# ProPrj_ESP32___2025-01-06.net
KiCad netlist of a schematic drawn in EasyEDA Pro
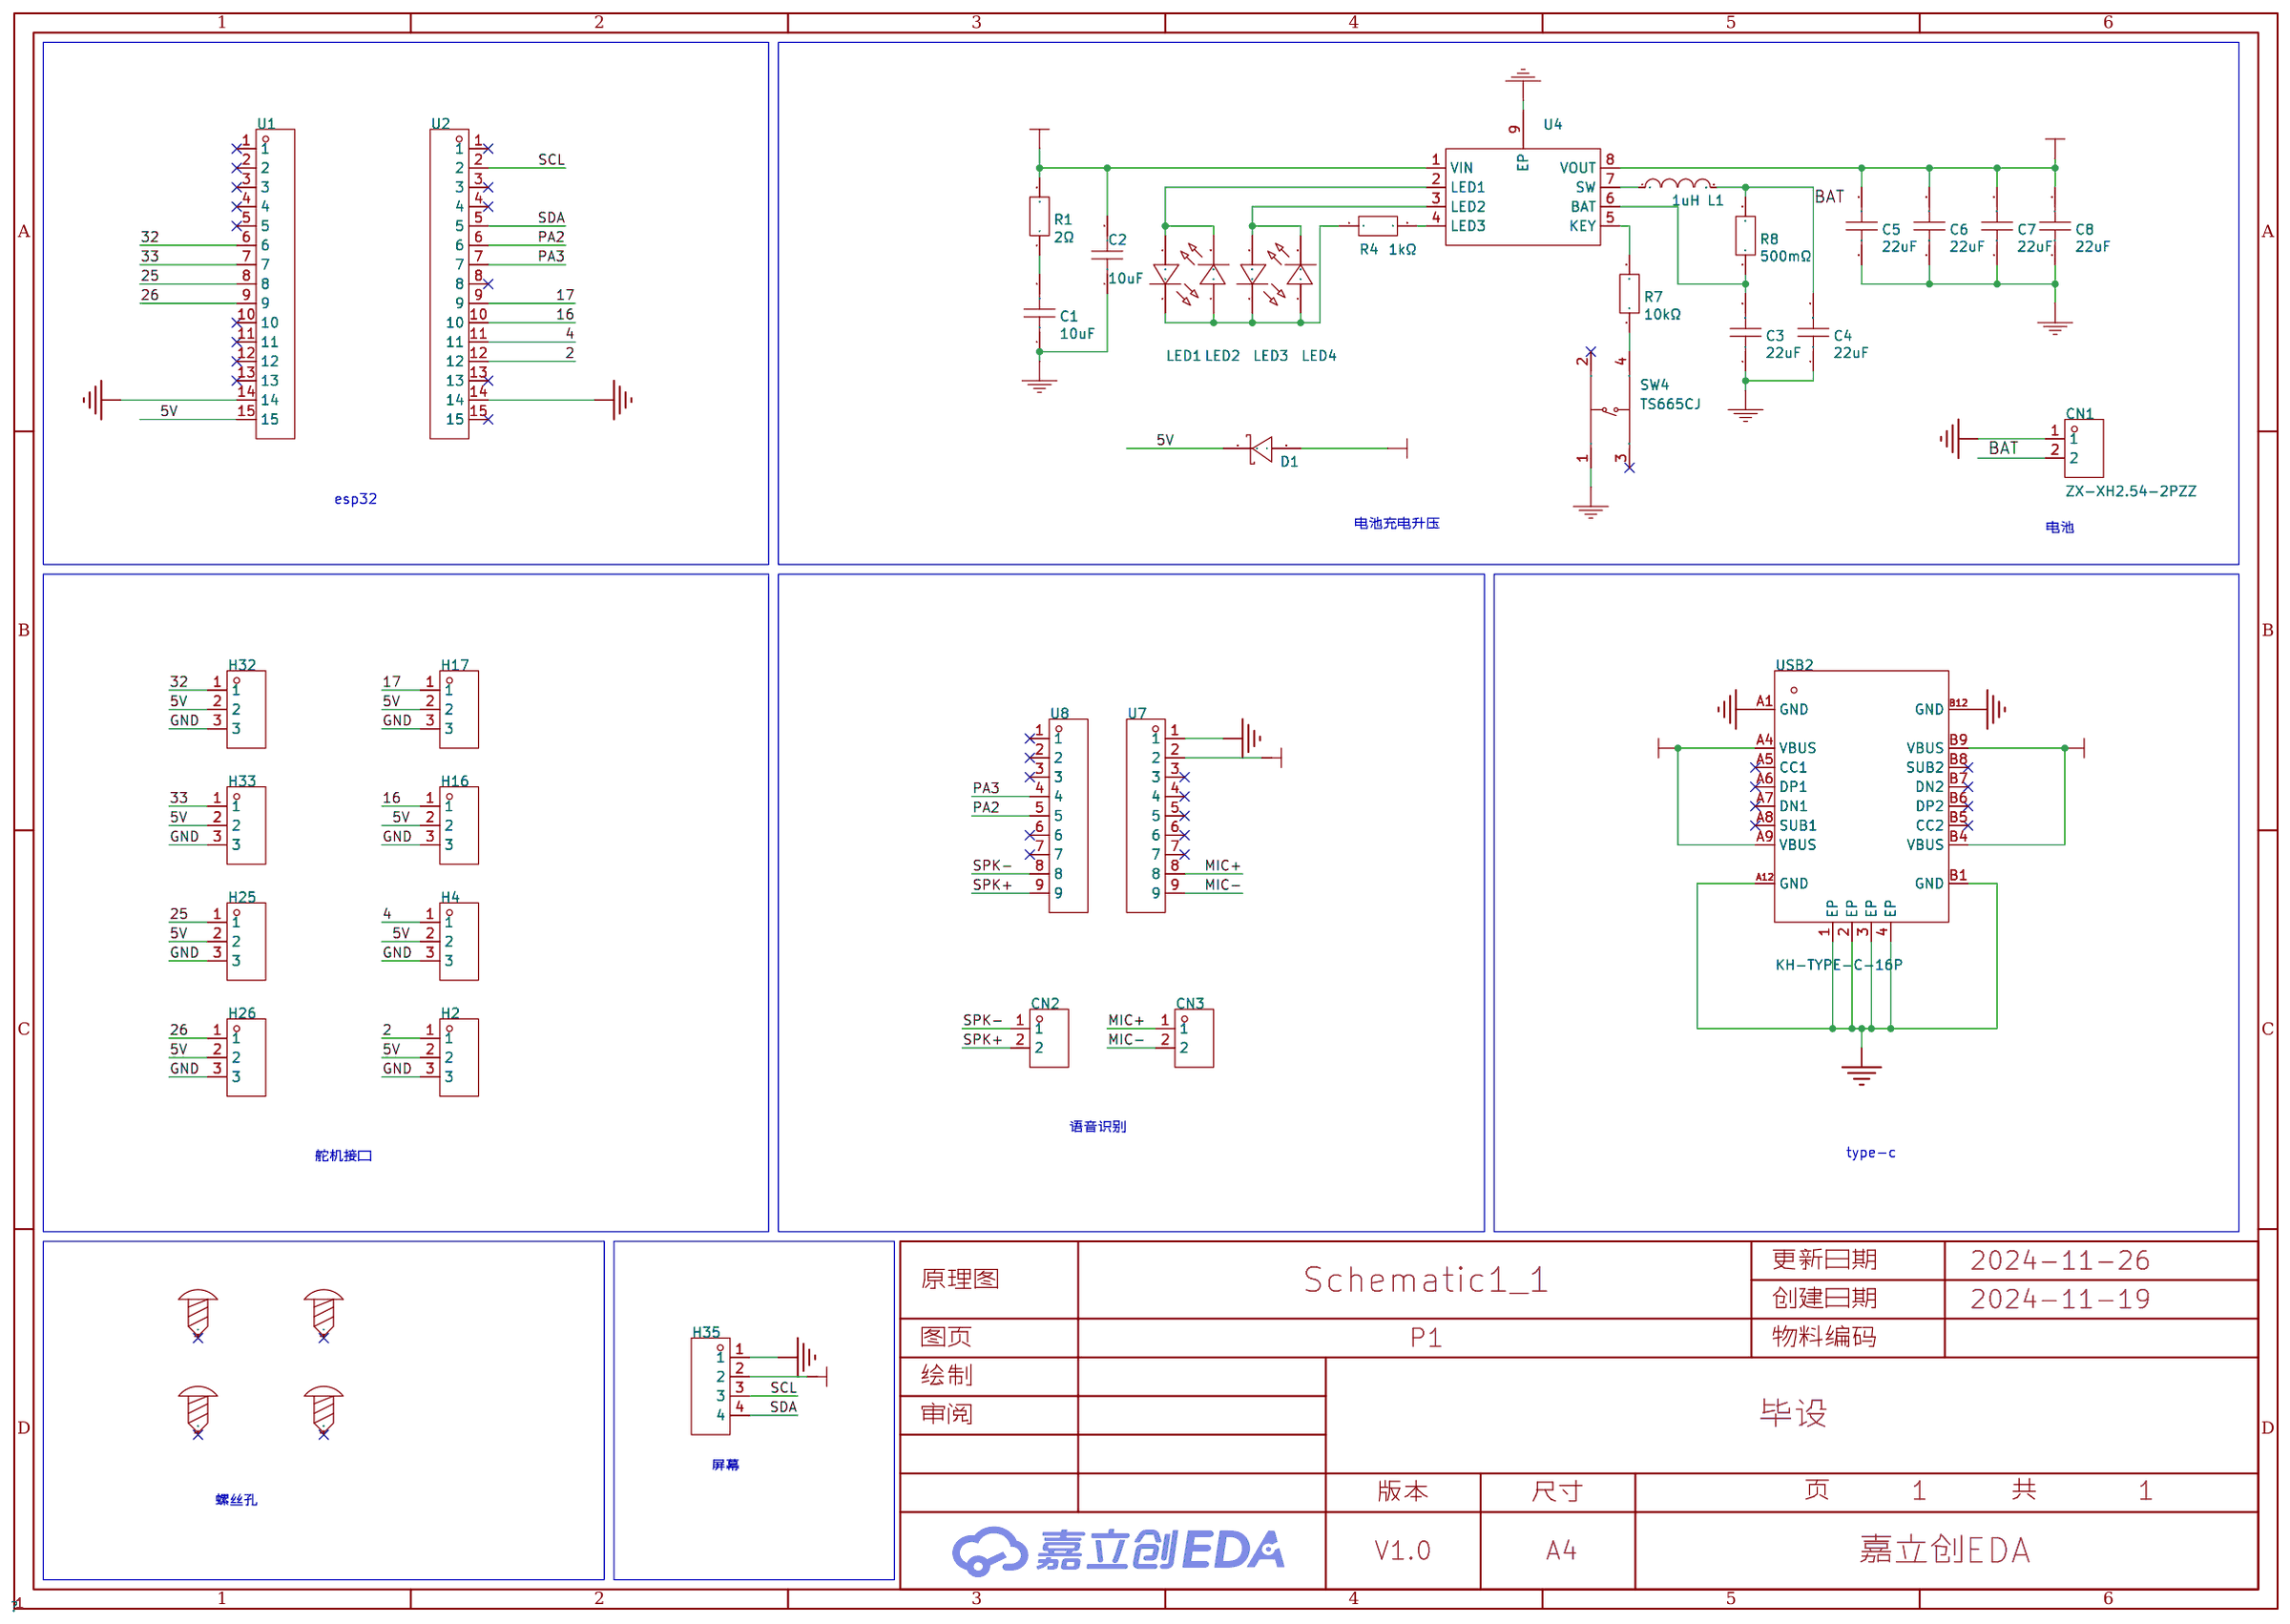
[diagram p0: schematic sheet]

(export (version "E")
  (design (tool "Eeschema 10.0.6"))
  (components
    (comp (ref "C1")
      (value "10uF")
      (fields (field (name "Manufacturer") "SAMSUNG(三星)"))
      (libsource (lib "easyedapro") (part "10u"))
    )
    (comp (ref "C2")
      (value "10uF")
      (fields (field (name "Manufacturer") "SAMSUNG(三星)"))
      (libsource (lib "easyedapro") (part "10u"))
    )
    (comp (ref "C3")
      (value "22uF")
      (fields (field (name "Manufacturer") "SAMSUNG(三星)"))
      (libsource (lib "easyedapro") (part "22u"))
    )
    (comp (ref "C4")
      (value "22uF")
      (fields (field (name "Manufacturer") "SAMSUNG(三星)"))
      (libsource (lib "easyedapro") (part "22u"))
    )
    (comp (ref "C5")
      (value "22uF")
      (fields (field (name "Manufacturer") "SAMSUNG(三星)"))
      (libsource (lib "easyedapro") (part "22u"))
    )
    (comp (ref "C6")
      (value "22uF")
      (fields (field (name "Manufacturer") "SAMSUNG(三星)"))
      (libsource (lib "easyedapro") (part "22u"))
    )
    (comp (ref "C7")
      (value "22uF")
      (fields (field (name "Manufacturer") "SAMSUNG(三星)"))
      (libsource (lib "easyedapro") (part "22u"))
    )
    (comp (ref "C8")
      (value "22uF")
      (fields (field (name "Manufacturer") "SAMSUNG(三星)"))
      (libsource (lib "easyedapro") (part "22u"))
    )
    (comp (ref "CN1")
      (value "ZX-XH2.54-2PZZ")
      (footprint "easyedapro:CONN-TH_2P-P2.50_HX25003-2A")
      (fields (field (name "Manufacturer") "Megastar(兆星)"))
      (libsource (lib "easyedapro") (part "ZX-XH2.54-2PZZ"))
    )
    (comp (ref "CN2")
      (value "ZX-XH2.54-2PZZ")
      (footprint "easyedapro:CONN-TH_2P-P2.50_HX25003-2A")
      (fields (field (name "Manufacturer") "Megastar(兆星)"))
      (libsource (lib "easyedapro") (part "ZX-XH2.54-2PZZ"))
    )
    (comp (ref "CN3")
      (value "ZX-XH2.54-2PZZ")
      (footprint "easyedapro:CONN-TH_2P-P2.50_HX25003-2A")
      (fields (field (name "Manufacturer") "Megastar(兆星)"))
      (libsource (lib "easyedapro") (part "ZX-XH2.54-2PZZ"))
    )
    (comp (ref "D1")
      (value "SS32")
      (fields (field (name "Manufacturer") "Jingdao"))
      (libsource (lib "easyedapro") (part "SS32"))
    )
    (comp (ref "H2")
      (value "PZ254V-11-03P")
      (footprint "easyedapro:HDR-TH_3P-P2.54-V-M")
      (fields (field (name "Manufacturer") "XFCN(兴飞)"))
      (libsource (lib "easyedapro") (part "PZ254V-11-03P_C2937625"))
    )
    (comp (ref "H4")
      (value "PZ254V-11-03P")
      (footprint "easyedapro:HDR-TH_3P-P2.54-V-M")
      (fields (field (name "Manufacturer") "XFCN(兴飞)"))
      (libsource (lib "easyedapro") (part "PZ254V-11-03P_C2937625"))
    )
    (comp (ref "H16")
      (value "PZ254V-11-03P")
      (footprint "easyedapro:HDR-TH_3P-P2.54-V-M")
      (fields (field (name "Manufacturer") "XFCN(兴飞)"))
      (libsource (lib "easyedapro") (part "PZ254V-11-03P_C2937625"))
    )
    (comp (ref "H17")
      (value "PZ254V-11-03P")
      (footprint "easyedapro:HDR-TH_3P-P2.54-V-M")
      (fields (field (name "Manufacturer") "XFCN(兴飞)"))
      (libsource (lib "easyedapro") (part "PZ254V-11-03P_C2937625"))
    )
    (comp (ref "H25")
      (value "PZ254V-11-03P")
      (footprint "easyedapro:HDR-TH_3P-P2.54-V-M")
      (fields (field (name "Manufacturer") "XFCN(兴飞)"))
      (libsource (lib "easyedapro") (part "PZ254V-11-03P_C2937625"))
    )
    (comp (ref "H26")
      (value "PZ254V-11-03P")
      (footprint "easyedapro:HDR-TH_3P-P2.54-V-M")
      (fields (field (name "Manufacturer") "XFCN(兴飞)"))
      (libsource (lib "easyedapro") (part "PZ254V-11-03P_C2937625"))
    )
    (comp (ref "H32")
      (value "PZ254V-11-03P")
      (footprint "easyedapro:HDR-TH_3P-P2.54-V-M")
      (fields (field (name "Manufacturer") "XFCN(兴飞)"))
      (libsource (lib "easyedapro") (part "PZ254V-11-03P_C2937625"))
    )
    (comp (ref "H33")
      (value "PZ254V-11-03P")
      (footprint "easyedapro:HDR-TH_3P-P2.54-V-M")
      (fields (field (name "Manufacturer") "XFCN(兴飞)"))
      (libsource (lib "easyedapro") (part "PZ254V-11-03P_C2937625"))
    )
    (comp (ref "H35")
      (value "2.54-1*4P母")
      (footprint "easyedapro:HDR-TH_4P-P2.54-V-F")
      (fields (field (name "Manufacturer") "BOOMELE(博穆精密)"))
      (libsource (lib "easyedapro") (part "2.54-1*4P母"))
    )
    (comp (ref "L1")
      (value "1uH")
      (fields (field (name "Manufacturer Part") "SPM6530T-1R0M120") (field (name "Manufacturer") "TDK"))
      (libsource (lib "easyedapro") (part "1uH"))
    )
    (comp (ref "LED1")
      (value "NCD0805G1")
      (fields (field (name "Manufacturer") "国星光电"))
      (libsource (lib "easyedapro") (part "0805_G"))
    )
    (comp (ref "LED2")
      (value "NCD0805G1")
      (fields (field (name "Manufacturer") "国星光电"))
      (libsource (lib "easyedapro") (part "0805_G"))
    )
    (comp (ref "LED3")
      (value "NCD0805G1")
      (fields (field (name "Manufacturer") "国星光电"))
      (libsource (lib "easyedapro") (part "0805_G"))
    )
    (comp (ref "LED4")
      (value "NCD0805G1")
      (fields (field (name "Manufacturer") "国星光电"))
      (libsource (lib "easyedapro") (part "0805_G"))
    )
    (comp (ref "R1")
      (value "2Ω")
      (fields (field (name "Manufacturer") "FOJAN(富捷)"))
      (libsource (lib "easyedapro") (part "2R"))
    )
    (comp (ref "R4")
      (value "1kΩ")
      (fields (field (name "Manufacturer") "UNI-ROYAL(厚声)"))
      (libsource (lib "easyedapro") (part "1K"))
    )
    (comp (ref "R7")
      (value "10kΩ")
      (fields (field (name "Manufacturer") "UNI-ROYAL(厚声)"))
      (libsource (lib "easyedapro") (part "10k"))
    )
    (comp (ref "R8")
      (value "500mΩ")
      (fields (field (name "Manufacturer") "FOJAN(富捷)"))
      (libsource (lib "easyedapro") (part "0.5R"))
    )
    (comp (ref "SCREW1")
      (value "~")
      (footprint "easyedapro:M4螺丝")
      (libsource (lib "easyedapro") (part "螺丝孔"))
    )
    (comp (ref "SCREW2")
      (value "~")
      (footprint "easyedapro:M4螺丝")
      (libsource (lib "easyedapro") (part "螺丝孔"))
    )
    (comp (ref "SCREW3")
      (value "~")
      (footprint "easyedapro:M4螺丝")
      (libsource (lib "easyedapro") (part "螺丝孔"))
    )
    (comp (ref "SCREW4")
      (value "~")
      (footprint "easyedapro:M4螺丝")
      (libsource (lib "easyedapro") (part "螺丝孔"))
    )
    (comp (ref "SW4")
      (value "TS665CJ")
      (footprint "easyedapro:SW-TH_4P-L6.0-W6.0-P4.50-LS6.5")
      (description "电路结构:单刀单掷;按钮形状:圆形按钮;安装方式:直插;开关长度:6mm;开关宽度:6mm;开关高度:5mm;触点电流:50mA;额定电压(DC):12V;带灯:-;机械寿命:-;")
      (fields (field (name "Manufacturer") "SHOU HAN(首韩)"))
      (libsource (lib "easyedapro") (part "TS665CJ"))
    )
    (comp (ref "U1")
      (value "KH-2.54FH-1X15P-H8.5")
      (footprint "easyedapro:HDR-TH_15P-P2.54-V-F")
      (fields (field (name "Manufacturer") "kinghelm(金航标)"))
      (libsource (lib "easyedapro") (part "KH-2.54FH-1X15P-H8.5"))
    )
    (comp (ref "U2")
      (value "KH-2.54FH-1X15P-H8.5")
      (footprint "easyedapro:HDR-TH_15P-P2.54-V-F")
      (fields (field (name "Manufacturer") "kinghelm(金航标)"))
      (libsource (lib "easyedapro") (part "KH-2.54FH-1X15P-H8.5"))
    )
    (comp (ref "U4")
      (value "IP5306")
      (fields (field (name "Manufacturer") "INJOINIC"))
      (libsource (lib "easyedapro") (part "IP5306"))
    )
    (comp (ref "U7")
      (value "PM254-1-09-Z-8.5")
      (footprint "easyedapro:HDR-TH_9P-P2.54-V-F")
      (fields (field (name "Manufacturer") "HCTL(华灿天禄)"))
      (libsource (lib "easyedapro") (part "PM254-1-09-Z-8.5"))
    )
    (comp (ref "U8")
      (value "PM254-1-09-Z-8.5")
      (footprint "easyedapro:HDR-TH_9P-P2.54-V-F")
      (fields (field (name "Manufacturer") "HCTL(华灿天禄)"))
      (libsource (lib "easyedapro") (part "PM254-1-09-Z-8.5"))
    )
    (comp (ref "USB2")
      (value "KH-TYPE-C-16P")
      (footprint "easyedapro:usb-c-smd_kh-type-c-16p")
      (description "连接器类型:Type-C;标准:-;公母:母;端口数量:1;触点数量:16P;安装方式:卧贴;额定电流 - 电源:3A;工作温度范围:-40°C~+85°C;")
      (fields (field (name "Manufacturer") "kinghelm(金航标)"))
      (libsource (lib "easyedapro") (part "KH-TYPE-C-16P"))
    )
  )
  (nets
    (net (code "1") (name "/2") (class "Default")
      (node (ref "H2") (pin "1") (pinfunction "1_1") (pintype "unspecified"))
      (node (ref "U2") (pin "12") (pinfunction "12_12") (pintype "unspecified"))
    )
    (net (code "2") (name "/4") (class "Default")
      (node (ref "H4") (pin "1") (pinfunction "1_1") (pintype "unspecified"))
      (node (ref "U2") (pin "11") (pinfunction "11_11") (pintype "unspecified"))
    )
    (net (code "3") (name "/16") (class "Default")
      (node (ref "H16") (pin "1") (pinfunction "1_1") (pintype "unspecified"))
      (node (ref "U2") (pin "10") (pinfunction "10_10") (pintype "unspecified"))
    )
    (net (code "4") (name "/17") (class "Default")
      (node (ref "H17") (pin "1") (pinfunction "1_1") (pintype "unspecified"))
      (node (ref "U2") (pin "9") (pinfunction "9_9") (pintype "unspecified"))
    )
    (net (code "5") (name "/25") (class "Default")
      (node (ref "H25") (pin "1") (pinfunction "1_1") (pintype "unspecified"))
      (node (ref "U1") (pin "8") (pinfunction "8_8") (pintype "unspecified"))
    )
    (net (code "6") (name "/26") (class "Default")
      (node (ref "H26") (pin "1") (pinfunction "1_1") (pintype "unspecified"))
      (node (ref "U1") (pin "9") (pinfunction "9_9") (pintype "unspecified"))
    )
    (net (code "7") (name "/32") (class "Default")
      (node (ref "H32") (pin "1") (pinfunction "1_1") (pintype "unspecified"))
      (node (ref "U1") (pin "6") (pinfunction "6_6") (pintype "unspecified"))
    )
    (net (code "8") (name "/33") (class "Default")
      (node (ref "H33") (pin "1") (pinfunction "1_1") (pintype "unspecified"))
      (node (ref "U1") (pin "7") (pinfunction "7_7") (pintype "unspecified"))
    )
    (net (code "9") (name "/BAT") (class "Default")
      (node (ref "C4") (pin "2") (pinfunction "2_2") (pintype "unspecified"))
      (node (ref "CN1") (pin "2") (pinfunction "2_2") (pintype "unspecified"))
      (node (ref "L1") (pin "2") (pinfunction "2_2") (pintype "unspecified"))
      (node (ref "R8") (pin "2") (pinfunction "2_2") (pintype "unspecified"))
    )
    (net (code "10") (name "/MIC+") (class "Default")
      (node (ref "CN3") (pin "1") (pinfunction "1_1") (pintype "unspecified"))
      (node (ref "U7") (pin "8") (pinfunction "8_8") (pintype "unspecified"))
    )
    (net (code "11") (name "/MIC-") (class "Default")
      (node (ref "CN3") (pin "2") (pinfunction "2_2") (pintype "unspecified"))
      (node (ref "U7") (pin "9") (pinfunction "9_9") (pintype "unspecified"))
    )
    (net (code "12") (name "/PA2") (class "Default")
      (node (ref "U2") (pin "6") (pinfunction "6_6") (pintype "unspecified"))
      (node (ref "U8") (pin "5") (pinfunction "5_5") (pintype "unspecified"))
    )
    (net (code "13") (name "/PA3") (class "Default")
      (node (ref "U2") (pin "7") (pinfunction "7_7") (pintype "unspecified"))
      (node (ref "U8") (pin "4") (pinfunction "4_4") (pintype "unspecified"))
    )
    (net (code "14") (name "/SCL") (class "Default")
      (node (ref "H35") (pin "3") (pinfunction "3_3") (pintype "unspecified"))
      (node (ref "U2") (pin "2") (pinfunction "2_2") (pintype "unspecified"))
    )
    (net (code "15") (name "/SDA") (class "Default")
      (node (ref "H35") (pin "4") (pinfunction "4_4") (pintype "unspecified"))
      (node (ref "U2") (pin "5") (pinfunction "5_5") (pintype "unspecified"))
    )
    (net (code "16") (name "/SPK+") (class "Default")
      (node (ref "CN2") (pin "2") (pinfunction "2_2") (pintype "unspecified"))
      (node (ref "U8") (pin "9") (pinfunction "9_9") (pintype "unspecified"))
    )
    (net (code "17") (name "/SPK-") (class "Default")
      (node (ref "CN2") (pin "1") (pinfunction "1_1") (pintype "unspecified"))
      (node (ref "U8") (pin "8") (pinfunction "8_8") (pintype "unspecified"))
    )
    (net (code "18") (name "5V") (class "Default")
      (node (ref "D1") (pin "1") (pinfunction "K_1") (pintype "unspecified"))
      (node (ref "H16") (pin "2") (pinfunction "2_2") (pintype "unspecified"))
      (node (ref "H17") (pin "2") (pinfunction "2_2") (pintype "unspecified"))
      (node (ref "H2") (pin "2") (pinfunction "2_2") (pintype "unspecified"))
      (node (ref "H25") (pin "2") (pinfunction "2_2") (pintype "unspecified"))
      (node (ref "H26") (pin "2") (pinfunction "2_2") (pintype "unspecified"))
      (node (ref "H32") (pin "2") (pinfunction "2_2") (pintype "unspecified"))
      (node (ref "H33") (pin "2") (pinfunction "2_2") (pintype "unspecified"))
      (node (ref "H35") (pin "2") (pinfunction "2_2") (pintype "unspecified"))
      (node (ref "H4") (pin "2") (pinfunction "2_2") (pintype "unspecified"))
      (node (ref "U1") (pin "15") (pinfunction "15_15") (pintype "unspecified"))
      (node (ref "U7") (pin "2") (pinfunction "2_2") (pintype "unspecified"))
    )
    (net (code "19") (name "5VOUT") (class "Default")
      (node (ref "C5") (pin "2") (pinfunction "2_2") (pintype "unspecified"))
      (node (ref "C6") (pin "2") (pinfunction "2_2") (pintype "unspecified"))
      (node (ref "C7") (pin "2") (pinfunction "2_2") (pintype "unspecified"))
      (node (ref "C8") (pin "2") (pinfunction "2_2") (pintype "unspecified"))
      (node (ref "D1") (pin "2") (pinfunction "A_2") (pintype "unspecified"))
      (node (ref "U4") (pin "8") (pinfunction "VOUT_8") (pintype "unspecified"))
    )
    (net (code "20") (name "GND") (class "Default")
      (node (ref "C1") (pin "1") (pinfunction "1_1") (pintype "unspecified"))
      (node (ref "C2") (pin "1") (pinfunction "1_1") (pintype "unspecified"))
      (node (ref "C3") (pin "1") (pinfunction "1_1") (pintype "unspecified"))
      (node (ref "C4") (pin "1") (pinfunction "1_1") (pintype "unspecified"))
      (node (ref "C5") (pin "1") (pinfunction "1_1") (pintype "unspecified"))
      (node (ref "C6") (pin "1") (pinfunction "1_1") (pintype "unspecified"))
      (node (ref "C7") (pin "1") (pinfunction "1_1") (pintype "unspecified"))
      (node (ref "C8") (pin "1") (pinfunction "1_1") (pintype "unspecified"))
      (node (ref "CN1") (pin "1") (pinfunction "1_1") (pintype "unspecified"))
      (node (ref "H16") (pin "3") (pinfunction "3_3") (pintype "unspecified"))
      (node (ref "H17") (pin "3") (pinfunction "3_3") (pintype "unspecified"))
      (node (ref "H2") (pin "3") (pinfunction "3_3") (pintype "unspecified"))
      (node (ref "H25") (pin "3") (pinfunction "3_3") (pintype "unspecified"))
      (node (ref "H26") (pin "3") (pinfunction "3_3") (pintype "unspecified"))
      (node (ref "H32") (pin "3") (pinfunction "3_3") (pintype "unspecified"))
      (node (ref "H33") (pin "3") (pinfunction "3_3") (pintype "unspecified"))
      (node (ref "H35") (pin "1") (pinfunction "1_1") (pintype "unspecified"))
      (node (ref "H4") (pin "3") (pinfunction "3_3") (pintype "unspecified"))
      (node (ref "SW4") (pin "1") (pinfunction "A_1") (pintype "unspecified"))
      (node (ref "U1") (pin "14") (pinfunction "14_14") (pintype "unspecified"))
      (node (ref "U2") (pin "14") (pinfunction "14_14") (pintype "unspecified"))
      (node (ref "U4") (pin "9") (pinfunction "EP_9") (pintype "unspecified"))
      (node (ref "U7") (pin "1") (pinfunction "1_1") (pintype "unspecified"))
      (node (ref "USB2") (pin "1") (pinfunction "EP_1") (pintype "unspecified"))
      (node (ref "USB2") (pin "2") (pinfunction "EP_2") (pintype "unspecified"))
      (node (ref "USB2") (pin "3") (pinfunction "EP_3") (pintype "unspecified"))
      (node (ref "USB2") (pin "4") (pinfunction "EP_4") (pintype "unspecified"))
      (node (ref "USB2") (pin "A1") (pinfunction "GND_A1") (pintype "unspecified"))
      (node (ref "USB2") (pin "A12") (pinfunction "GND_A12") (pintype "unspecified"))
      (node (ref "USB2") (pin "B1") (pinfunction "GND_B1") (pintype "unspecified"))
      (node (ref "USB2") (pin "B12") (pinfunction "GND_B12") (pintype "unspecified"))
    )
    (net (code "21") (name "Net-(C1-Pad2)") (class "Default")
      (node (ref "C1") (pin "2") (pinfunction "2_2") (pintype "unspecified"))
      (node (ref "R1") (pin "1") (pinfunction "1_1") (pintype "unspecified"))
    )
    (net (code "22") (name "Net-(LED1-Pad2)") (class "Default")
      (node (ref "LED1") (pin "2") (pinfunction "2_2") (pintype "unspecified"))
      (node (ref "LED2") (pin "1") (pinfunction "1_1") (pintype "unspecified"))
      (node (ref "LED3") (pin "2") (pinfunction "2_2") (pintype "unspecified"))
      (node (ref "LED4") (pin "1") (pinfunction "1_1") (pintype "unspecified"))
      (node (ref "R4") (pin "1") (pinfunction "1_1") (pintype "unspecified"))
    )
    (net (code "23") (name "Net-(SW4-D)") (class "Default")
      (node (ref "R7") (pin "1") (pinfunction "1_1") (pintype "unspecified"))
      (node (ref "SW4") (pin "4") (pinfunction "D_4") (pintype "unspecified"))
    )
    (net (code "24") (name "Net-(U4-BAT)") (class "Default")
      (node (ref "C3") (pin "2") (pinfunction "2_2") (pintype "unspecified"))
      (node (ref "R8") (pin "1") (pinfunction "1_1") (pintype "unspecified"))
      (node (ref "U4") (pin "6") (pinfunction "BAT_6") (pintype "unspecified"))
    )
    (net (code "25") (name "Net-(U4-KEY)") (class "Default")
      (node (ref "R7") (pin "2") (pinfunction "2_2") (pintype "unspecified"))
      (node (ref "U4") (pin "5") (pinfunction "KEY_5") (pintype "unspecified"))
    )
    (net (code "26") (name "Net-(U4-LED1)") (class "Default")
      (node (ref "LED1") (pin "1") (pinfunction "1_1") (pintype "unspecified"))
      (node (ref "LED2") (pin "2") (pinfunction "2_2") (pintype "unspecified"))
      (node (ref "U4") (pin "2") (pinfunction "LED1_2") (pintype "unspecified"))
    )
    (net (code "27") (name "Net-(U4-LED2)") (class "Default")
      (node (ref "LED3") (pin "1") (pinfunction "1_1") (pintype "unspecified"))
      (node (ref "LED4") (pin "2") (pinfunction "2_2") (pintype "unspecified"))
      (node (ref "U4") (pin "3") (pinfunction "LED2_3") (pintype "unspecified"))
    )
    (net (code "28") (name "Net-(U4-LED3)") (class "Default")
      (node (ref "R4") (pin "2") (pinfunction "2_2") (pintype "unspecified"))
      (node (ref "U4") (pin "4") (pinfunction "LED3_4") (pintype "unspecified"))
    )
    (net (code "29") (name "Net-(U4-SW)") (class "Default")
      (node (ref "L1") (pin "1") (pinfunction "1_1") (pintype "unspecified"))
      (node (ref "U4") (pin "7") (pinfunction "SW_7") (pintype "unspecified"))
    )
    (net (code "30") (name "VIN") (class "Default")
      (node (ref "C2") (pin "2") (pinfunction "2_2") (pintype "unspecified"))
      (node (ref "R1") (pin "2") (pinfunction "2_2") (pintype "unspecified"))
      (node (ref "U4") (pin "1") (pinfunction "VIN_1") (pintype "unspecified"))
      (node (ref "USB2") (pin "A4") (pinfunction "VBUS_A4") (pintype "unspecified"))
      (node (ref "USB2") (pin "A9") (pinfunction "VBUS_A9") (pintype "unspecified"))
      (node (ref "USB2") (pin "B4") (pinfunction "VBUS_B4") (pintype "unspecified"))
      (node (ref "USB2") (pin "B9") (pinfunction "VBUS_B9") (pintype "unspecified"))
    )
    (net (code "31") (name "unconnected-(SCREW1-Pad1)") (class "Default")
      (node (ref "SCREW1") (pin "1") (pinfunction "1_1") (pintype "input+no_connect"))
    )
    (net (code "32") (name "unconnected-(SCREW2-Pad1)") (class "Default")
      (node (ref "SCREW2") (pin "1") (pinfunction "1_1") (pintype "input+no_connect"))
    )
    (net (code "33") (name "unconnected-(SCREW3-Pad1)") (class "Default")
      (node (ref "SCREW3") (pin "1") (pinfunction "1_1") (pintype "input+no_connect"))
    )
    (net (code "34") (name "unconnected-(SCREW4-Pad1)") (class "Default")
      (node (ref "SCREW4") (pin "1") (pinfunction "1_1") (pintype "input+no_connect"))
    )
    (net (code "35") (name "unconnected-(SW4-B-Pad2)") (class "Default")
      (node (ref "SW4") (pin "2") (pinfunction "B_2") (pintype "unspecified+no_connect"))
    )
    (net (code "36") (name "unconnected-(SW4-C-Pad3)") (class "Default")
      (node (ref "SW4") (pin "3") (pinfunction "C_3") (pintype "unspecified+no_connect"))
    )
    (net (code "37") (name "unconnected-(U1-Pad1)") (class "Default")
      (node (ref "U1") (pin "1") (pinfunction "1_1") (pintype "unspecified+no_connect"))
    )
    (net (code "38") (name "unconnected-(U1-Pad2)") (class "Default")
      (node (ref "U1") (pin "2") (pinfunction "2_2") (pintype "unspecified+no_connect"))
    )
    (net (code "39") (name "unconnected-(U1-Pad3)") (class "Default")
      (node (ref "U1") (pin "3") (pinfunction "3_3") (pintype "unspecified+no_connect"))
    )
    (net (code "40") (name "unconnected-(U1-Pad4)") (class "Default")
      (node (ref "U1") (pin "4") (pinfunction "4_4") (pintype "unspecified+no_connect"))
    )
    (net (code "41") (name "unconnected-(U1-Pad5)") (class "Default")
      (node (ref "U1") (pin "5") (pinfunction "5_5") (pintype "unspecified+no_connect"))
    )
    (net (code "42") (name "unconnected-(U1-Pad10)") (class "Default")
      (node (ref "U1") (pin "10") (pinfunction "10_10") (pintype "unspecified+no_connect"))
    )
    (net (code "43") (name "unconnected-(U1-Pad11)") (class "Default")
      (node (ref "U1") (pin "11") (pinfunction "11_11") (pintype "unspecified+no_connect"))
    )
    (net (code "44") (name "unconnected-(U1-Pad12)") (class "Default")
      (node (ref "U1") (pin "12") (pinfunction "12_12") (pintype "unspecified+no_connect"))
    )
    (net (code "45") (name "unconnected-(U1-Pad13)") (class "Default")
      (node (ref "U1") (pin "13") (pinfunction "13_13") (pintype "unspecified+no_connect"))
    )
    (net (code "46") (name "unconnected-(U2-Pad1)") (class "Default")
      (node (ref "U2") (pin "1") (pinfunction "1_1") (pintype "unspecified+no_connect"))
    )
    (net (code "47") (name "unconnected-(U2-Pad3)") (class "Default")
      (node (ref "U2") (pin "3") (pinfunction "3_3") (pintype "unspecified+no_connect"))
    )
    (net (code "48") (name "unconnected-(U2-Pad4)") (class "Default")
      (node (ref "U2") (pin "4") (pinfunction "4_4") (pintype "unspecified+no_connect"))
    )
    (net (code "49") (name "unconnected-(U2-Pad8)") (class "Default")
      (node (ref "U2") (pin "8") (pinfunction "8_8") (pintype "unspecified+no_connect"))
    )
    (net (code "50") (name "unconnected-(U2-Pad13)") (class "Default")
      (node (ref "U2") (pin "13") (pinfunction "13_13") (pintype "unspecified+no_connect"))
    )
    (net (code "51") (name "unconnected-(U2-Pad15)") (class "Default")
      (node (ref "U2") (pin "15") (pinfunction "15_15") (pintype "unspecified+no_connect"))
    )
    (net (code "52") (name "unconnected-(U7-Pad3)") (class "Default")
      (node (ref "U7") (pin "3") (pinfunction "3_3") (pintype "unspecified+no_connect"))
    )
    (net (code "53") (name "unconnected-(U7-Pad4)") (class "Default")
      (node (ref "U7") (pin "4") (pinfunction "4_4") (pintype "unspecified+no_connect"))
    )
    (net (code "54") (name "unconnected-(U7-Pad5)") (class "Default")
      (node (ref "U7") (pin "5") (pinfunction "5_5") (pintype "unspecified+no_connect"))
    )
    (net (code "55") (name "unconnected-(U7-Pad6)") (class "Default")
      (node (ref "U7") (pin "6") (pinfunction "6_6") (pintype "unspecified+no_connect"))
    )
    (net (code "56") (name "unconnected-(U7-Pad7)") (class "Default")
      (node (ref "U7") (pin "7") (pinfunction "7_7") (pintype "unspecified+no_connect"))
    )
    (net (code "57") (name "unconnected-(U8-Pad1)") (class "Default")
      (node (ref "U8") (pin "1") (pinfunction "1_1") (pintype "unspecified+no_connect"))
    )
    (net (code "58") (name "unconnected-(U8-Pad2)") (class "Default")
      (node (ref "U8") (pin "2") (pinfunction "2_2") (pintype "unspecified+no_connect"))
    )
    (net (code "59") (name "unconnected-(U8-Pad3)") (class "Default")
      (node (ref "U8") (pin "3") (pinfunction "3_3") (pintype "unspecified+no_connect"))
    )
    (net (code "60") (name "unconnected-(U8-Pad6)") (class "Default")
      (node (ref "U8") (pin "6") (pinfunction "6_6") (pintype "unspecified+no_connect"))
    )
    (net (code "61") (name "unconnected-(U8-Pad7)") (class "Default")
      (node (ref "U8") (pin "7") (pinfunction "7_7") (pintype "unspecified+no_connect"))
    )
    (net (code "62") (name "unconnected-(USB2-CC1-PadA5)") (class "Default")
      (node (ref "USB2") (pin "A5") (pinfunction "CC1_A5") (pintype "unspecified+no_connect"))
    )
    (net (code "63") (name "unconnected-(USB2-CC2-PadB5)") (class "Default")
      (node (ref "USB2") (pin "B5") (pinfunction "CC2_B5") (pintype "unspecified+no_connect"))
    )
    (net (code "64") (name "unconnected-(USB2-DN1-PadA7)") (class "Default")
      (node (ref "USB2") (pin "A7") (pinfunction "DN1_A7") (pintype "unspecified+no_connect"))
    )
    (net (code "65") (name "unconnected-(USB2-DN2-PadB7)") (class "Default")
      (node (ref "USB2") (pin "B7") (pinfunction "DN2_B7") (pintype "unspecified+no_connect"))
    )
    (net (code "66") (name "unconnected-(USB2-DP1-PadA6)") (class "Default")
      (node (ref "USB2") (pin "A6") (pinfunction "DP1_A6") (pintype "unspecified+no_connect"))
    )
    (net (code "67") (name "unconnected-(USB2-DP2-PadB6)") (class "Default")
      (node (ref "USB2") (pin "B6") (pinfunction "DP2_B6") (pintype "unspecified+no_connect"))
    )
    (net (code "68") (name "unconnected-(USB2-SUB1-PadA8)") (class "Default")
      (node (ref "USB2") (pin "A8") (pinfunction "SUB1_A8") (pintype "unspecified+no_connect"))
    )
    (net (code "69") (name "unconnected-(USB2-SUB2-PadB8)") (class "Default")
      (node (ref "USB2") (pin "B8") (pinfunction "SUB2_B8") (pintype "unspecified+no_connect"))
    )
  )
)
